# ehomeGeneral_v1.net
KiCad netlist of a schematic drawn in EAGLE
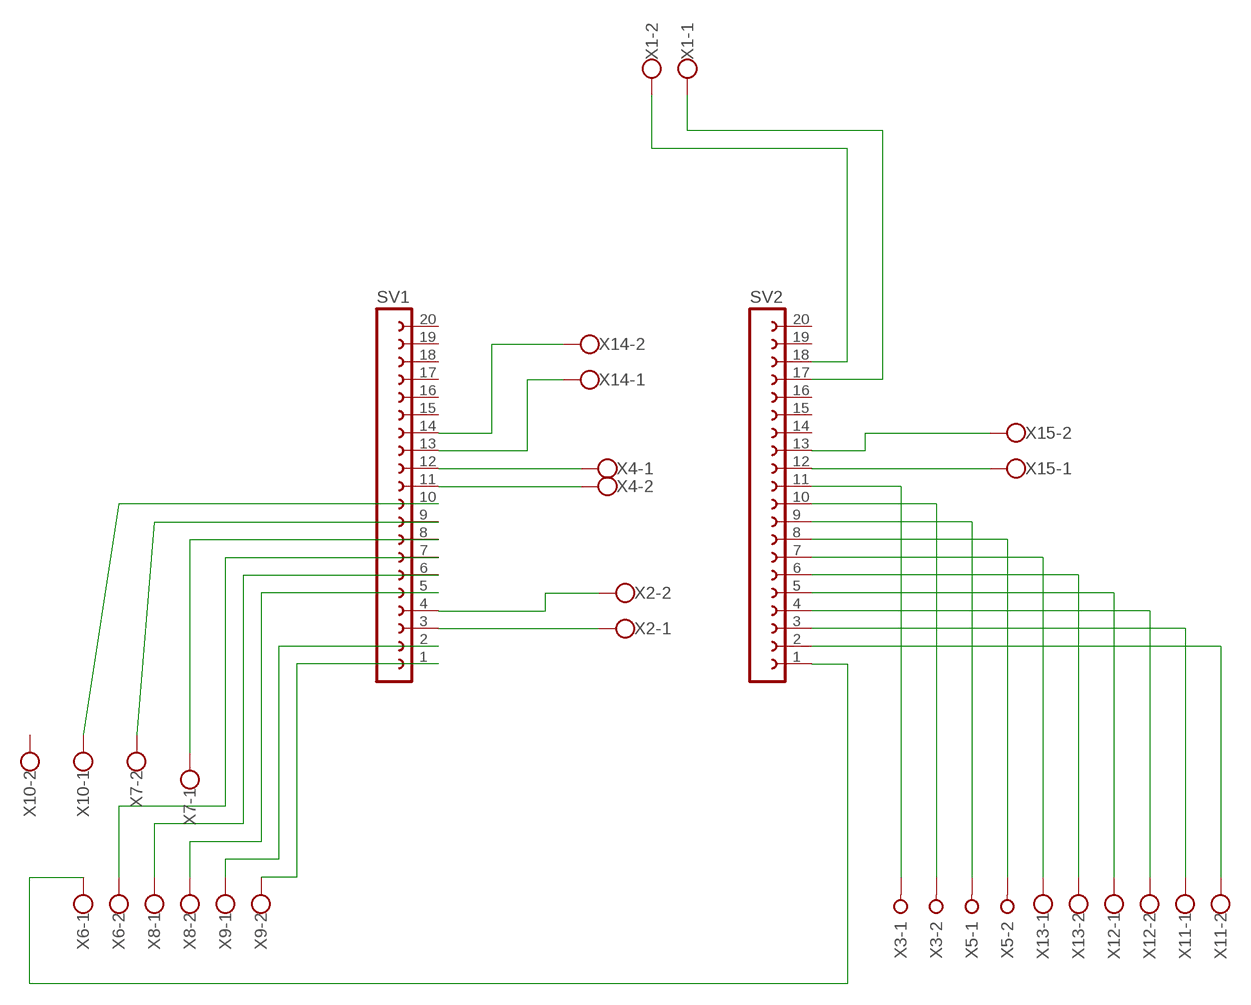
[diagram p0: schematic, sheet 1]

(export (version "E")
  (design (tool "Eeschema 10.0.6"))
  (components
    (comp (ref "SV1")
      (value "FE20-1")
      (footprint "eagle-import:FE20")
      (libsource (lib "eagle-import") (part "FE20-1"))
    )
    (comp (ref "SV2")
      (value "FE20-1")
      (footprint "eagle-import:FE20")
      (libsource (lib "eagle-import") (part "FE20-1"))
    )
    (comp (ref "X1")
      (value "W237-102")
      (footprint "eagle-import:W237-102")
      (fields (field (name "MPN") "237-102"))
      (libsource (lib "eagle-import") (part "W237-102"))
    )
    (comp (ref "X2")
      (value "W237-102")
      (footprint "eagle-import:W237-102")
      (fields (field (name "MPN") "237-102"))
      (libsource (lib "eagle-import") (part "W237-102"))
    )
    (comp (ref "X3")
      (value "W237-02P")
      (footprint "eagle-import:W237-132")
      (libsource (lib "eagle-import") (part "W237-02P"))
    )
    (comp (ref "X4")
      (value "W237-102")
      (footprint "eagle-import:W237-102")
      (fields (field (name "MPN") "237-102"))
      (libsource (lib "eagle-import") (part "W237-102"))
    )
    (comp (ref "X5")
      (value "W237-02P")
      (footprint "eagle-import:W237-132")
      (libsource (lib "eagle-import") (part "W237-02P"))
    )
    (comp (ref "X6")
      (value "W237-102")
      (footprint "eagle-import:W237-102")
      (fields (field (name "MPN") "237-102"))
      (libsource (lib "eagle-import") (part "W237-102"))
    )
    (comp (ref "X7")
      (value "W237-102")
      (footprint "eagle-import:W237-102")
      (fields (field (name "MPN") "237-102"))
      (libsource (lib "eagle-import") (part "W237-102"))
    )
    (comp (ref "X8")
      (value "W237-102")
      (footprint "eagle-import:W237-102")
      (fields (field (name "MPN") "237-102"))
      (libsource (lib "eagle-import") (part "W237-102"))
    )
    (comp (ref "X9")
      (value "W237-102")
      (footprint "eagle-import:W237-102")
      (fields (field (name "MPN") "237-102"))
      (libsource (lib "eagle-import") (part "W237-102"))
    )
    (comp (ref "X10")
      (value "W237-102")
      (footprint "eagle-import:W237-102")
      (fields (field (name "MPN") "237-102"))
      (libsource (lib "eagle-import") (part "W237-102"))
    )
    (comp (ref "X11")
      (value "W237-102")
      (footprint "eagle-import:W237-102")
      (fields (field (name "MPN") "237-102"))
      (libsource (lib "eagle-import") (part "W237-102"))
    )
    (comp (ref "X12")
      (value "W237-102")
      (footprint "eagle-import:W237-102")
      (fields (field (name "MPN") "237-102"))
      (libsource (lib "eagle-import") (part "W237-102"))
    )
    (comp (ref "X13")
      (value "W237-102")
      (footprint "eagle-import:W237-102")
      (fields (field (name "MPN") "237-102"))
      (libsource (lib "eagle-import") (part "W237-102"))
    )
    (comp (ref "X14")
      (value "W237-102")
      (footprint "eagle-import:W237-102")
      (fields (field (name "MPN") "237-102"))
      (libsource (lib "eagle-import") (part "W237-102"))
    )
    (comp (ref "X15")
      (value "W237-102")
      (footprint "eagle-import:W237-102")
      (fields (field (name "MPN") "237-102"))
      (libsource (lib "eagle-import") (part "W237-102"))
    )
  )
  (nets
    (net (code "1") (name "Net-(X1A-KL)") (class "Default")
      (node (ref "SV2") (pin "17") (pinfunction "17_17") (pintype "passive"))
      (node (ref "X1") (pin "1") (pinfunction "KL_1") (pintype "passive"))
    )
    (net (code "2") (name "Net-(X1B-KL)") (class "Default")
      (node (ref "SV2") (pin "18") (pinfunction "18_18") (pintype "passive"))
      (node (ref "X1") (pin "2") (pinfunction "KL_2") (pintype "passive"))
    )
    (net (code "3") (name "Net-(X2A-KL)") (class "Default")
      (node (ref "SV1") (pin "3") (pinfunction "3_3") (pintype "passive"))
      (node (ref "X2") (pin "1") (pinfunction "KL_1") (pintype "passive"))
    )
    (net (code "4") (name "Net-(X2B-KL)") (class "Default")
      (node (ref "SV1") (pin "4") (pinfunction "4_4") (pintype "passive"))
      (node (ref "X2") (pin "2") (pinfunction "KL_2") (pintype "passive"))
    )
    (net (code "5") (name "Net-(X3A-KL)") (class "Default")
      (node (ref "SV2") (pin "11") (pinfunction "11_11") (pintype "passive"))
      (node (ref "X3") (pin "1") (pinfunction "KL_1") (pintype "passive"))
    )
    (net (code "6") (name "Net-(X3B-KL)") (class "Default")
      (node (ref "SV2") (pin "10") (pinfunction "10_10") (pintype "passive"))
      (node (ref "X3") (pin "2") (pinfunction "KL_2") (pintype "passive"))
    )
    (net (code "7") (name "Net-(X4A-KL)") (class "Default")
      (node (ref "SV1") (pin "12") (pinfunction "12_12") (pintype "passive"))
      (node (ref "X4") (pin "1") (pinfunction "KL_1") (pintype "passive"))
    )
    (net (code "8") (name "Net-(X4B-KL)") (class "Default")
      (node (ref "SV1") (pin "11") (pinfunction "11_11") (pintype "passive"))
      (node (ref "X4") (pin "2") (pinfunction "KL_2") (pintype "passive"))
    )
    (net (code "9") (name "Net-(X5A-KL)") (class "Default")
      (node (ref "SV2") (pin "9") (pinfunction "9_9") (pintype "passive"))
      (node (ref "X5") (pin "1") (pinfunction "KL_1") (pintype "passive"))
    )
    (net (code "10") (name "Net-(X5B-KL)") (class "Default")
      (node (ref "SV2") (pin "8") (pinfunction "8_8") (pintype "passive"))
      (node (ref "X5") (pin "2") (pinfunction "KL_2") (pintype "passive"))
    )
    (net (code "11") (name "Net-(X6A-KL)") (class "Default")
      (node (ref "SV2") (pin "1") (pinfunction "1_1") (pintype "passive"))
      (node (ref "X6") (pin "1") (pinfunction "KL_1") (pintype "passive"))
    )
    (net (code "12") (name "Net-(X6B-KL)") (class "Default")
      (node (ref "SV1") (pin "7") (pinfunction "7_7") (pintype "passive"))
      (node (ref "X6") (pin "2") (pinfunction "KL_2") (pintype "passive"))
    )
    (net (code "13") (name "Net-(X7A-KL)") (class "Default")
      (node (ref "SV1") (pin "8") (pinfunction "8_8") (pintype "passive"))
      (node (ref "X7") (pin "1") (pinfunction "KL_1") (pintype "passive"))
    )
    (net (code "14") (name "Net-(X7B-KL)") (class "Default")
      (node (ref "SV1") (pin "9") (pinfunction "9_9") (pintype "passive"))
      (node (ref "X7") (pin "2") (pinfunction "KL_2") (pintype "passive"))
    )
    (net (code "15") (name "Net-(X8A-KL)") (class "Default")
      (node (ref "SV1") (pin "6") (pinfunction "6_6") (pintype "passive"))
      (node (ref "X8") (pin "1") (pinfunction "KL_1") (pintype "passive"))
    )
    (net (code "16") (name "Net-(X8B-KL)") (class "Default")
      (node (ref "SV1") (pin "5") (pinfunction "5_5") (pintype "passive"))
      (node (ref "X8") (pin "2") (pinfunction "KL_2") (pintype "passive"))
    )
    (net (code "17") (name "Net-(X9A-KL)") (class "Default")
      (node (ref "SV1") (pin "2") (pinfunction "2_2") (pintype "passive"))
      (node (ref "X9") (pin "1") (pinfunction "KL_1") (pintype "passive"))
    )
    (net (code "18") (name "Net-(X9B-KL)") (class "Default")
      (node (ref "SV1") (pin "1") (pinfunction "1_1") (pintype "passive"))
      (node (ref "X9") (pin "2") (pinfunction "KL_2") (pintype "passive"))
    )
    (net (code "19") (name "Net-(X10A-KL)") (class "Default")
      (node (ref "SV1") (pin "10") (pinfunction "10_10") (pintype "passive"))
      (node (ref "X10") (pin "1") (pinfunction "KL_1") (pintype "passive"))
    )
    (net (code "20") (name "Net-(X11A-KL)") (class "Default")
      (node (ref "SV2") (pin "3") (pinfunction "3_3") (pintype "passive"))
      (node (ref "X11") (pin "1") (pinfunction "KL_1") (pintype "passive"))
    )
    (net (code "21") (name "Net-(X11B-KL)") (class "Default")
      (node (ref "SV2") (pin "2") (pinfunction "2_2") (pintype "passive"))
      (node (ref "X11") (pin "2") (pinfunction "KL_2") (pintype "passive"))
    )
    (net (code "22") (name "Net-(X12A-KL)") (class "Default")
      (node (ref "SV2") (pin "5") (pinfunction "5_5") (pintype "passive"))
      (node (ref "X12") (pin "1") (pinfunction "KL_1") (pintype "passive"))
    )
    (net (code "23") (name "Net-(X12B-KL)") (class "Default")
      (node (ref "SV2") (pin "4") (pinfunction "4_4") (pintype "passive"))
      (node (ref "X12") (pin "2") (pinfunction "KL_2") (pintype "passive"))
    )
    (net (code "24") (name "Net-(X13A-KL)") (class "Default")
      (node (ref "SV2") (pin "7") (pinfunction "7_7") (pintype "passive"))
      (node (ref "X13") (pin "1") (pinfunction "KL_1") (pintype "passive"))
    )
    (net (code "25") (name "Net-(X13B-KL)") (class "Default")
      (node (ref "SV2") (pin "6") (pinfunction "6_6") (pintype "passive"))
      (node (ref "X13") (pin "2") (pinfunction "KL_2") (pintype "passive"))
    )
    (net (code "26") (name "Net-(X14A-KL)") (class "Default")
      (node (ref "SV1") (pin "13") (pinfunction "13_13") (pintype "passive"))
      (node (ref "X14") (pin "1") (pinfunction "KL_1") (pintype "passive"))
    )
    (net (code "27") (name "Net-(X14B-KL)") (class "Default")
      (node (ref "SV1") (pin "14") (pinfunction "14_14") (pintype "passive"))
      (node (ref "X14") (pin "2") (pinfunction "KL_2") (pintype "passive"))
    )
    (net (code "28") (name "Net-(X15A-KL)") (class "Default")
      (node (ref "SV2") (pin "12") (pinfunction "12_12") (pintype "passive"))
      (node (ref "X15") (pin "1") (pinfunction "KL_1") (pintype "passive"))
    )
    (net (code "29") (name "Net-(X15B-KL)") (class "Default")
      (node (ref "SV2") (pin "13") (pinfunction "13_13") (pintype "passive"))
      (node (ref "X15") (pin "2") (pinfunction "KL_2") (pintype "passive"))
    )
    (net (code "30") (name "unconnected-(SV1-Pad15)") (class "Default")
      (node (ref "SV1") (pin "15") (pinfunction "15_15") (pintype "passive"))
    )
    (net (code "31") (name "unconnected-(SV1-Pad16)") (class "Default")
      (node (ref "SV1") (pin "16") (pinfunction "16_16") (pintype "passive"))
    )
    (net (code "32") (name "unconnected-(SV1-Pad17)") (class "Default")
      (node (ref "SV1") (pin "17") (pinfunction "17_17") (pintype "passive"))
    )
    (net (code "33") (name "unconnected-(SV1-Pad18)") (class "Default")
      (node (ref "SV1") (pin "18") (pinfunction "18_18") (pintype "passive"))
    )
    (net (code "34") (name "unconnected-(SV1-Pad19)") (class "Default")
      (node (ref "SV1") (pin "19") (pinfunction "19_19") (pintype "passive"))
    )
    (net (code "35") (name "unconnected-(SV1-Pad20)") (class "Default")
      (node (ref "SV1") (pin "20") (pinfunction "20_20") (pintype "passive"))
    )
    (net (code "36") (name "unconnected-(SV2-Pad14)") (class "Default")
      (node (ref "SV2") (pin "14") (pinfunction "14_14") (pintype "passive"))
    )
    (net (code "37") (name "unconnected-(SV2-Pad15)") (class "Default")
      (node (ref "SV2") (pin "15") (pinfunction "15_15") (pintype "passive"))
    )
    (net (code "38") (name "unconnected-(SV2-Pad16)") (class "Default")
      (node (ref "SV2") (pin "16") (pinfunction "16_16") (pintype "passive"))
    )
    (net (code "39") (name "unconnected-(SV2-Pad19)") (class "Default")
      (node (ref "SV2") (pin "19") (pinfunction "19_19") (pintype "passive"))
    )
    (net (code "40") (name "unconnected-(SV2-Pad20)") (class "Default")
      (node (ref "SV2") (pin "20") (pinfunction "20_20") (pintype "passive"))
    )
    (net (code "41") (name "unconnected-(X10B-KL-Pad2)") (class "Default")
      (node (ref "X10") (pin "2") (pinfunction "KL_2") (pintype "passive"))
    )
  )
)
